# Power_Supply_Section.net
KiCad netlist of a schematic drawn in Altium Designer
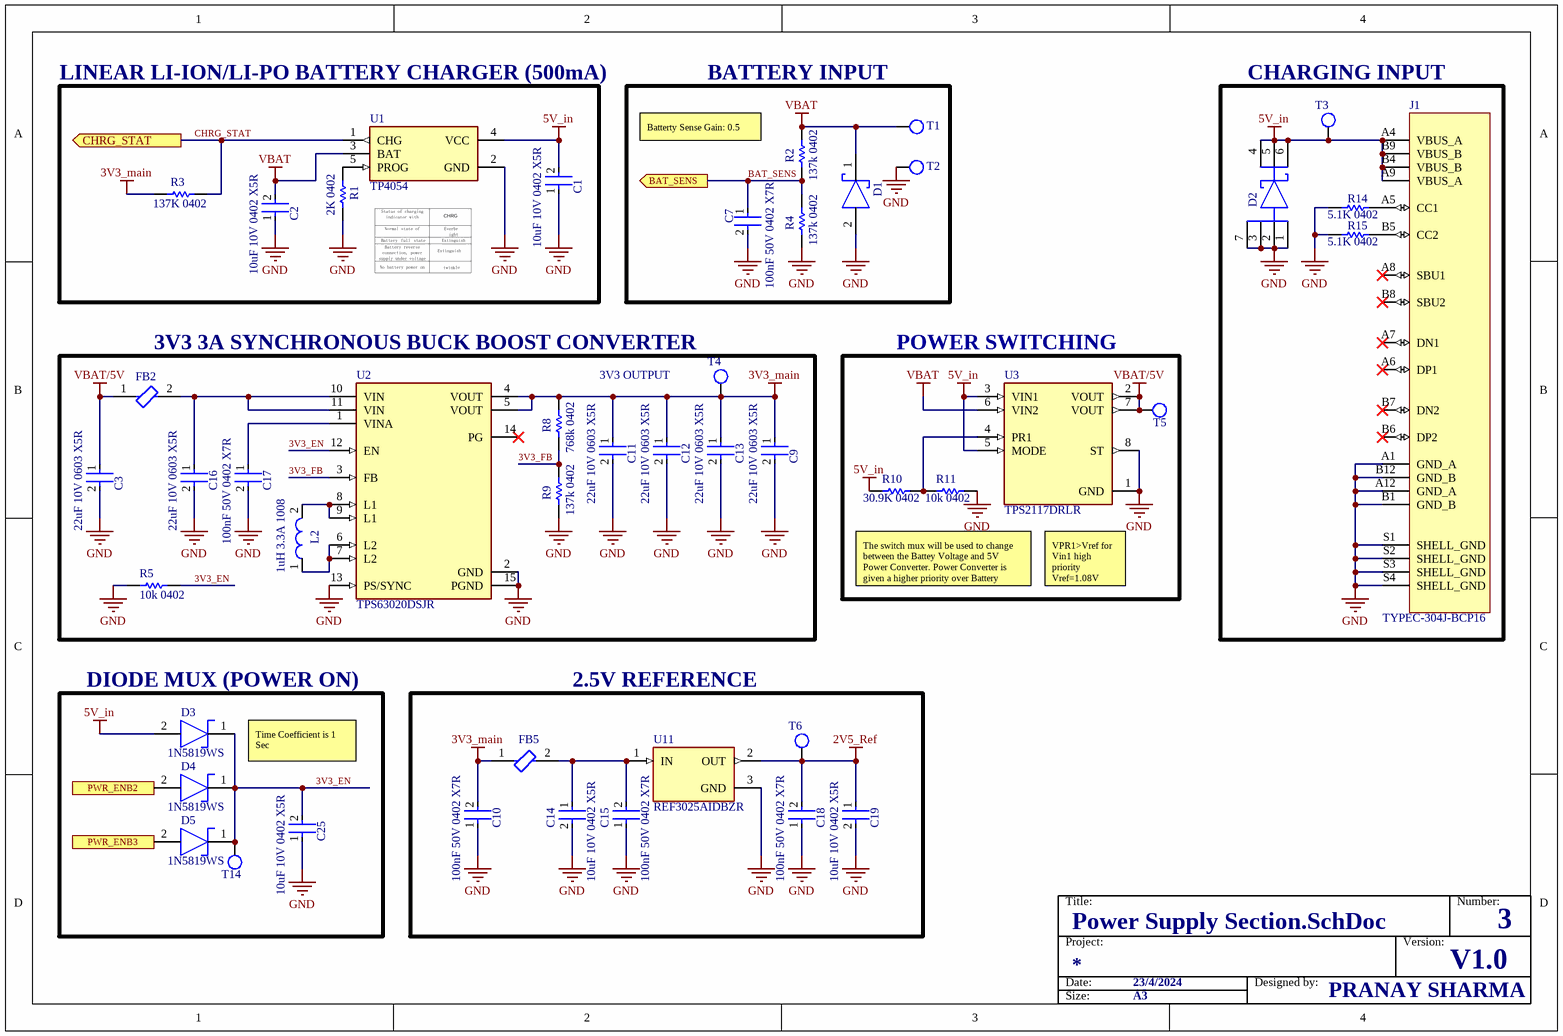
[diagram p0: Power Supply Section.SchDoc]

(export (version "E")
  (design (tool "Eeschema 10.0.6"))
  (components
    (comp (ref "C1")
      (value "10uF 10V 0402 X5R")
      (footprint "Res, Cap, Ind, LED, FB_Lib:0402 IPC CLASS C CAPACITOR")
      (libsource (lib "Capacitor_Lib") (part "10uF 10V 0402 X5R"))
    )
    (comp (ref "C2")
      (value "10uF 10V 0402 X5R")
      (footprint "Res, Cap, Ind, LED, FB_Lib:0402 IPC CLASS C CAPACITOR")
      (libsource (lib "Capacitor_Lib") (part "10uF 10V 0402 X5R"))
    )
    (comp (ref "C3")
      (value "22uF 10V 0603 X5R")
      (footprint "Res, Cap, Ind, LED, FB_Lib:0603 IPC CLASS C CAPACITOR")
      (libsource (lib "Capacitor_Lib") (part "22uF 10V 0603 X5R"))
    )
    (comp (ref "C7")
      (value "100nF 50V 0402 X7R")
      (footprint "Res, Cap, Ind, LED, FB_Lib:0402 IPC CLASS C CAPACITOR")
      (libsource (lib "Capacitor_Lib") (part "100nF 50V 0402 X7R"))
    )
    (comp (ref "C9")
      (value "22uF 10V 0603 X5R")
      (footprint "Res, Cap, Ind, LED, FB_Lib:0603 IPC CLASS C CAPACITOR")
      (libsource (lib "Capacitor_Lib") (part "22uF 10V 0603 X5R"))
    )
    (comp (ref "C10")
      (value "100nF 50V 0402 X7R")
      (footprint "Res, Cap, Ind, LED, FB_Lib:0402 IPC CLASS C CAPACITOR")
      (libsource (lib "Capacitor_Lib") (part "100nF 50V 0402 X7R"))
    )
    (comp (ref "C11")
      (value "22uF 10V 0603 X5R")
      (footprint "Res, Cap, Ind, LED, FB_Lib:0603 IPC CLASS C CAPACITOR")
      (libsource (lib "Capacitor_Lib") (part "22uF 10V 0603 X5R"))
    )
    (comp (ref "C12")
      (value "22uF 10V 0603 X5R")
      (footprint "Res, Cap, Ind, LED, FB_Lib:0603 IPC CLASS C CAPACITOR")
      (libsource (lib "Capacitor_Lib") (part "22uF 10V 0603 X5R"))
    )
    (comp (ref "C13")
      (value "22uF 10V 0603 X5R")
      (footprint "Res, Cap, Ind, LED, FB_Lib:0603 IPC CLASS C CAPACITOR")
      (libsource (lib "Capacitor_Lib") (part "22uF 10V 0603 X5R"))
    )
    (comp (ref "C14")
      (value "10uF 10V 0402 X5R")
      (footprint "Res, Cap, Ind, LED, FB_Lib:0402 IPC CLASS C CAPACITOR")
      (libsource (lib "Capacitor_Lib") (part "10uF 10V 0402 X5R"))
    )
    (comp (ref "C15")
      (value "100nF 50V 0402 X7R")
      (footprint "Res, Cap, Ind, LED, FB_Lib:0402 IPC CLASS C CAPACITOR")
      (libsource (lib "Capacitor_Lib") (part "100nF 50V 0402 X7R"))
    )
    (comp (ref "C16")
      (value "22uF 10V 0603 X5R")
      (footprint "Res, Cap, Ind, LED, FB_Lib:0603 IPC CLASS C CAPACITOR")
      (libsource (lib "Capacitor_Lib") (part "22uF 10V 0603 X5R"))
    )
    (comp (ref "C17")
      (value "100nF 50V 0402 X7R")
      (footprint "Res, Cap, Ind, LED, FB_Lib:0402 IPC CLASS C CAPACITOR")
      (libsource (lib "Capacitor_Lib") (part "100nF 50V 0402 X7R"))
    )
    (comp (ref "C18")
      (value "100nF 50V 0402 X7R")
      (footprint "Res, Cap, Ind, LED, FB_Lib:0402 IPC CLASS C CAPACITOR")
      (libsource (lib "Capacitor_Lib") (part "100nF 50V 0402 X7R"))
    )
    (comp (ref "C19")
      (value "10uF 10V 0402 X5R")
      (footprint "Res, Cap, Ind, LED, FB_Lib:0402 IPC CLASS C CAPACITOR")
      (libsource (lib "Capacitor_Lib") (part "10uF 10V 0402 X5R"))
    )
    (comp (ref "C25")
      (value "10uF 10V 0402 X5R")
      (footprint "Res, Cap, Ind, LED, FB_Lib:0402 IPC CLASS C CAPACITOR")
      (libsource (lib "Capacitor_Lib") (part "10uF 10V 0402 X5R"))
    )
    (comp (ref "D1")
      (value "SP3031-01ETG")
      (footprint "Res, Cap, Ind, LED, FB_Lib:SOD882 IPC-C")
      (libsource (lib "Diodes_Lib") (part "SP3031-01ETG"))
    )
    (comp (ref "D2")
      (value "TVS0500DRVR")
      (footprint "Res, Cap, Ind, LED, FB_Lib:DRV0006A IPC-C")
      (libsource (lib "Diodes_Lib") (part "TVS0500DRVR"))
    )
    (comp (ref "D3")
      (value "1N5819WS")
      (footprint "Res, Cap, Ind, LED, FB_Lib:SOD-323 IPC-C")
      (libsource (lib "Diodes_Lib") (part "1N5819WS"))
    )
    (comp (ref "D4")
      (value "1N5819WS")
      (footprint "Res, Cap, Ind, LED, FB_Lib:SOD-323 IPC-C")
      (libsource (lib "Diodes_Lib") (part "1N5819WS"))
    )
    (comp (ref "D5")
      (value "1N5819WS")
      (footprint "Res, Cap, Ind, LED, FB_Lib:SOD-323 IPC-C")
      (libsource (lib "Diodes_Lib") (part "1N5819WS"))
    )
    (comp (ref "FB2")
      (value "BLM21SP111SN1D")
      (footprint "Res, Cap, Ind, LED, FB_Lib:0603 IPC CLASS C FERRITE BEAD")
      (libsource (lib "Ferrite_Bead_Lib") (part "BLM21SP111SN1D"))
    )
    (comp (ref "FB5")
      (value "BLM15AX102SN1D")
      (footprint "Res, Cap, Ind, LED, FB_Lib:0402 IPC CLASS C FERRITE BEAD")
      (libsource (lib "Ferrite_Bead_Lib") (part "BLM15AX102SN1D"))
    )
    (comp (ref "J1")
      (value "TYPEC-304J-BCP16")
      (footprint "VALCON_CSP-USC16-TR")
      (libsource (lib "V1.0") (part "USB Type C"))
    )
    (comp (ref "L2")
      (value "1uH 3.3A 1008")
      (footprint "Res, Cap, Ind, LED, FB_Lib:1008 Inductor IPC-C")
      (libsource (lib "Inductor_Lib") (part "DFE252012F-1R0M=P2"))
    )
    (comp (ref "R1")
      (value "2K 0402")
      (footprint "Res, Cap, Ind, LED, FB_Lib:0402 IPC CLASS C RESISTOR")
      (libsource (lib "Resistor_Lib") (part "2K 1% 0402"))
    )
    (comp (ref "R2")
      (value "137k 0402")
      (footprint "Res, Cap, Ind, LED, FB_Lib:0402 IPC CLASS C RESISTOR")
      (libsource (lib "Resistor_Lib") (part "10k 1% 0402"))
    )
    (comp (ref "R3")
      (value "137K 0402")
      (footprint "Res, Cap, Ind, LED, FB_Lib:0402 IPC CLASS C RESISTOR")
      (libsource (lib "Resistor_Lib") (part "137K 1% 0402"))
    )
    (comp (ref "R4")
      (value "137k 0402")
      (footprint "Res, Cap, Ind, LED, FB_Lib:0402 IPC CLASS C RESISTOR")
      (libsource (lib "Resistor_Lib") (part "10k 1% 0402"))
    )
    (comp (ref "R5")
      (value "10k 0402")
      (footprint "Res, Cap, Ind, LED, FB_Lib:0402 IPC CLASS C RESISTOR")
      (libsource (lib "Resistor_Lib") (part "10k 1% 0402"))
    )
    (comp (ref "R8")
      (value "768k 0402")
      (footprint "Res, Cap, Ind, LED, FB_Lib:0402 IPC CLASS C RESISTOR")
      (libsource (lib "Resistor_Lib") (part "10k 1% 0402"))
    )
    (comp (ref "R9")
      (value "137k 0402")
      (footprint "Res, Cap, Ind, LED, FB_Lib:0402 IPC CLASS C RESISTOR")
      (libsource (lib "Resistor_Lib") (part "10k 1% 0402"))
    )
    (comp (ref "R10")
      (value "30.9K 0402")
      (footprint "Res, Cap, Ind, LED, FB_Lib:0402 IPC CLASS C RESISTOR")
      (libsource (lib "Resistor_Lib") (part "30.9K 1%  0402"))
    )
    (comp (ref "R11")
      (value "10k 0402")
      (footprint "Res, Cap, Ind, LED, FB_Lib:0402 IPC CLASS C RESISTOR")
      (libsource (lib "Resistor_Lib") (part "10k 1% 0402"))
    )
    (comp (ref "R14")
      (value "5.1K 0402")
      (footprint "Res, Cap, Ind, LED, FB_Lib:0402 IPC CLASS C RESISTOR")
      (libsource (lib "Resistor_Lib") (part "5.1K 1% 0402"))
    )
    (comp (ref "R15")
      (value "5.1K 0402")
      (footprint "Res, Cap, Ind, LED, FB_Lib:0402 IPC CLASS C RESISTOR")
      (libsource (lib "Resistor_Lib") (part "5.1K 1% 0402"))
    )
    (comp (ref "T1")
      (value "Test Point TH")
      (footprint "Miscellaneous_Lib:Test Point TH")
      (libsource (lib "Miscellaneous_Lib") (part "Test Point TH"))
    )
    (comp (ref "T2")
      (value "Test Point TH")
      (footprint "Miscellaneous_Lib:Test Point TH")
      (libsource (lib "Miscellaneous_Lib") (part "Test Point TH"))
    )
    (comp (ref "T3")
      (value "TP")
      (footprint "Miscellaneous_Lib:Testpoint1")
      (libsource (lib "Miscellaneous_Lib") (part "Testpoint1"))
    )
    (comp (ref "T4")
      (value "TP")
      (footprint "Miscellaneous_Lib:Testpoint1")
      (libsource (lib "Miscellaneous_Lib") (part "Testpoint1"))
    )
    (comp (ref "T5")
      (value "TP")
      (footprint "Miscellaneous_Lib:Testpoint1")
      (libsource (lib "Miscellaneous_Lib") (part "Testpoint1"))
    )
    (comp (ref "T6")
      (value "TP")
      (footprint "Miscellaneous_Lib:Testpoint1")
      (libsource (lib "Miscellaneous_Lib") (part "Testpoint1"))
    )
    (comp (ref "T14")
      (value "TP")
      (footprint "Miscellaneous_Lib:Testpoint1")
      (libsource (lib "Miscellaneous_Lib") (part "Testpoint1"))
    )
    (comp (ref "U1")
      (value "TP4054")
      (footprint "Integrated_Circuits_Lib:DBV0005A IPC-C")
      (libsource (lib "Integrated_Circuits_Lib") (part "TP4054"))
    )
    (comp (ref "U2")
      (value "TPS63020DSJR")
      (footprint "FP-DSJ0014A-MFG")
      (libsource (lib "Altium Content Vault") (part "ca84f4b88d1e031d86a58c77b9c066d"))
    )
    (comp (ref "U3")
      (value "TPS2117DRLR")
      (footprint "Integrated_Circuits_Lib:DRL0008A IPC-C")
      (libsource (lib "Integrated_Circuits_Lib") (part "TPS2117DRLR"))
    )
    (comp (ref "U11")
      (value "REF3025AIDBZR")
      (footprint "Integrated_Circuits_Lib:SOT23-IPC_C")
      (libsource (lib "Integrated_Circuits_Lib") (part "REF3025AIDBZR"))
    )
  )
  (nets
    (net (code "1") (name "/3V3_EN") (class "Default")
      (node (ref "C25") (pin "2") (pinfunction "2_2") (pintype "passive"))
      (node (ref "D3") (pin "1") (pinfunction "C_1") (pintype "passive"))
      (node (ref "D4") (pin "1") (pinfunction "C_1") (pintype "passive"))
      (node (ref "D5") (pin "1") (pinfunction "C_1") (pintype "passive"))
      (node (ref "R5") (pin "1") (pinfunction "1_1") (pintype "passive"))
      (node (ref "T14") (pin "0") (pinfunction "0_0") (pintype "passive"))
      (node (ref "U2") (pin "12") (pinfunction "EN_12") (pintype "input"))
    )
    (net (code "2") (name "/3V3_FB") (class "Default")
      (node (ref "R8") (pin "2") (pinfunction "2_2") (pintype "passive"))
      (node (ref "R9") (pin "2") (pinfunction "2_2") (pintype "passive"))
      (node (ref "U2") (pin "3") (pinfunction "FB_3") (pintype "input"))
    )
    (net (code "3") (name "/BAT_SENS") (class "Default")
      (node (ref "C7") (pin "1") (pinfunction "1_1") (pintype "passive"))
      (node (ref "R2") (pin "1") (pinfunction "1_1") (pintype "passive"))
      (node (ref "R4") (pin "2") (pinfunction "2_2") (pintype "passive"))
    )
    (net (code "4") (name "/CHRG_STAT") (class "Default")
      (node (ref "R3") (pin "2") (pinfunction "2_2") (pintype "passive"))
      (node (ref "U1") (pin "1") (pinfunction "CHG_1") (pintype "output"))
    )
    (net (code "5") (name "/PWR_ENB2") (class "Default")
      (node (ref "D4") (pin "2") (pinfunction "A_2") (pintype "passive"))
    )
    (net (code "6") (name "/PWR_ENB3") (class "Default")
      (node (ref "D5") (pin "2") (pinfunction "A_2") (pintype "passive"))
    )
    (net (code "7") (name "2V5_Ref") (class "Default")
      (node (ref "C18") (pin "2") (pinfunction "2_2") (pintype "passive"))
      (node (ref "C19") (pin "1") (pinfunction "1_1") (pintype "passive"))
      (node (ref "T6") (pin "0") (pinfunction "0_0") (pintype "passive"))
      (node (ref "U11") (pin "2") (pinfunction "OUT_2") (pintype "output"))
    )
    (net (code "8") (name "3V3_main") (class "Default")
      (node (ref "C10") (pin "2") (pinfunction "2_2") (pintype "passive"))
      (node (ref "C11") (pin "1") (pinfunction "1_1") (pintype "passive"))
      (node (ref "C12") (pin "1") (pinfunction "1_1") (pintype "passive"))
      (node (ref "C13") (pin "1") (pinfunction "1_1") (pintype "passive"))
      (node (ref "C9") (pin "1") (pinfunction "1_1") (pintype "passive"))
      (node (ref "FB5") (pin "1") (pinfunction "1_1") (pintype "passive"))
      (node (ref "R3") (pin "1") (pinfunction "1_1") (pintype "passive"))
      (node (ref "R8") (pin "1") (pinfunction "1_1") (pintype "passive"))
      (node (ref "T4") (pin "0") (pinfunction "0_0") (pintype "passive"))
      (node (ref "U2") (pin "4") (pinfunction "VOUT_4") (pintype "power_in"))
      (node (ref "U2") (pin "5") (pinfunction "VOUT_5") (pintype "power_in"))
    )
    (net (code "9") (name "5V_in") (class "Default")
      (node (ref "C1") (pin "2") (pinfunction "2_2") (pintype "passive"))
      (node (ref "D2") (pin "4") (pinfunction "4_4") (pintype "passive"))
      (node (ref "D2") (pin "5") (pinfunction "5_5") (pintype "passive"))
      (node (ref "D2") (pin "6") (pinfunction "6_6") (pintype "passive"))
      (node (ref "D3") (pin "2") (pinfunction "A_2") (pintype "passive"))
      (node (ref "J1") (pin "A4") (pinfunction "VBUS_A_A4") (pintype "power_in"))
      (node (ref "J1") (pin "A9") (pinfunction "VBUS_A_A9") (pintype "power_in"))
      (node (ref "J1") (pin "B4") (pinfunction "VBUS_B_B4") (pintype "power_in"))
      (node (ref "J1") (pin "B9") (pinfunction "VBUS_B_B9") (pintype "power_in"))
      (node (ref "R10") (pin "2") (pinfunction "2_2") (pintype "passive"))
      (node (ref "T3") (pin "0") (pinfunction "0_0") (pintype "passive"))
      (node (ref "U1") (pin "4") (pinfunction "VCC_4") (pintype "power_in"))
      (node (ref "U3") (pin "3") (pinfunction "VIN1_3") (pintype "input"))
      (node (ref "U3") (pin "5") (pinfunction "MODE_5") (pintype "input"))
    )
    (net (code "10") (name "GND") (class "Default")
      (node (ref "C1") (pin "1") (pinfunction "1_1") (pintype "passive"))
      (node (ref "C10") (pin "1") (pinfunction "1_1") (pintype "passive"))
      (node (ref "C11") (pin "2") (pinfunction "2_2") (pintype "passive"))
      (node (ref "C12") (pin "2") (pinfunction "2_2") (pintype "passive"))
      (node (ref "C13") (pin "2") (pinfunction "2_2") (pintype "passive"))
      (node (ref "C14") (pin "2") (pinfunction "2_2") (pintype "passive"))
      (node (ref "C15") (pin "1") (pinfunction "1_1") (pintype "passive"))
      (node (ref "C16") (pin "2") (pinfunction "2_2") (pintype "passive"))
      (node (ref "C17") (pin "2") (pinfunction "2_2") (pintype "passive"))
      (node (ref "C18") (pin "1") (pinfunction "1_1") (pintype "passive"))
      (node (ref "C19") (pin "2") (pinfunction "2_2") (pintype "passive"))
      (node (ref "C2") (pin "1") (pinfunction "1_1") (pintype "passive"))
      (node (ref "C25") (pin "1") (pinfunction "1_1") (pintype "passive"))
      (node (ref "C3") (pin "2") (pinfunction "2_2") (pintype "passive"))
      (node (ref "C7") (pin "2") (pinfunction "2_2") (pintype "passive"))
      (node (ref "C9") (pin "2") (pinfunction "2_2") (pintype "passive"))
      (node (ref "D1") (pin "2") (pinfunction "A_2") (pintype "passive"))
      (node (ref "D2") (pin "1") (pinfunction "C_1") (pintype "passive"))
      (node (ref "D2") (pin "2") (pinfunction "A_2") (pintype "passive"))
      (node (ref "D2") (pin "3") (pinfunction "3_3") (pintype "passive"))
      (node (ref "D2") (pin "7") (pinfunction "7_7") (pintype "passive"))
      (node (ref "J1") (pin "A1") (pinfunction "GND_A_A1") (pintype "power_in"))
      (node (ref "J1") (pin "A12") (pinfunction "GND_A_A12") (pintype "power_in"))
      (node (ref "J1") (pin "B1") (pinfunction "GND_B_B1") (pintype "power_in"))
      (node (ref "J1") (pin "B12") (pinfunction "GND_B_B12") (pintype "power_in"))
      (node (ref "J1") (pin "S1") (pinfunction "SHELL_GND_S1") (pintype "power_in"))
      (node (ref "J1") (pin "S2") (pinfunction "SHELL_GND_S2") (pintype "power_in"))
      (node (ref "J1") (pin "S3") (pinfunction "SHELL_GND_S3") (pintype "power_in"))
      (node (ref "J1") (pin "S4") (pinfunction "SHELL_GND_S4") (pintype "power_in"))
      (node (ref "R1") (pin "2") (pinfunction "2_2") (pintype "passive"))
      (node (ref "R11") (pin "1") (pinfunction "1_1") (pintype "passive"))
      (node (ref "R14") (pin "1") (pinfunction "1_1") (pintype "passive"))
      (node (ref "R15") (pin "1") (pinfunction "1_1") (pintype "passive"))
      (node (ref "R4") (pin "1") (pinfunction "1_1") (pintype "passive"))
      (node (ref "R5") (pin "2") (pinfunction "2_2") (pintype "passive"))
      (node (ref "R9") (pin "1") (pinfunction "1_1") (pintype "passive"))
      (node (ref "T2") (pin "0") (pinfunction "0_0") (pintype "passive"))
      (node (ref "U1") (pin "2") (pinfunction "GND_2") (pintype "power_in"))
      (node (ref "U11") (pin "3") (pinfunction "GND_3") (pintype "power_in"))
      (node (ref "U2") (pin "13") (pinfunction "PS/SYNC_13") (pintype "input"))
      (node (ref "U2") (pin "15") (pinfunction "PGND_15") (pintype "power_in"))
      (node (ref "U2") (pin "2") (pinfunction "GND_2") (pintype "power_in"))
      (node (ref "U3") (pin "1") (pinfunction "GND_1") (pintype "power_in"))
      (node (ref "U3") (pin "8") (pinfunction "ST_8") (pintype "output"))
    )
    (net (code "11") (name "Net-(C16-Pad1)") (class "Default")
      (node (ref "C16") (pin "1") (pinfunction "1_1") (pintype "passive"))
      (node (ref "FB2") (pin "2") (pinfunction "2_2") (pintype "passive"))
      (node (ref "U2") (pin "10") (pinfunction "VIN_10") (pintype "power_in"))
      (node (ref "U2") (pin "11") (pinfunction "VIN_11") (pintype "power_in"))
    )
    (net (code "12") (name "Net-(J1-CC1)") (class "Default")
      (node (ref "J1") (pin "A5") (pinfunction "CC1_A5") (pintype "bidirectional"))
      (node (ref "R14") (pin "2") (pinfunction "2_2") (pintype "passive"))
    )
    (net (code "13") (name "Net-(J1-CC2)") (class "Default")
      (node (ref "J1") (pin "B5") (pinfunction "CC2_B5") (pintype "bidirectional"))
      (node (ref "R15") (pin "2") (pinfunction "2_2") (pintype "passive"))
    )
    (net (code "14") (name "Net-(L2-Pad1)") (class "Default")
      (node (ref "L2") (pin "1") (pinfunction "1_1") (pintype "passive"))
      (node (ref "U2") (pin "6") (pinfunction "L2_6") (pintype "input"))
      (node (ref "U2") (pin "7") (pinfunction "L2_7") (pintype "input"))
    )
    (net (code "15") (name "Net-(L2-Pad2)") (class "Default")
      (node (ref "L2") (pin "2") (pinfunction "2_2") (pintype "passive"))
      (node (ref "U2") (pin "8") (pinfunction "L1_8") (pintype "input"))
      (node (ref "U2") (pin "9") (pinfunction "L1_9") (pintype "input"))
    )
    (net (code "16") (name "Net-(U1-PROG)") (class "Default")
      (node (ref "R1") (pin "1") (pinfunction "1_1") (pintype "passive"))
      (node (ref "U1") (pin "5") (pinfunction "PROG_5") (pintype "input"))
    )
    (net (code "17") (name "Net-(U2-VINA)") (class "Default")
      (node (ref "C17") (pin "1") (pinfunction "1_1") (pintype "passive"))
      (node (ref "U2") (pin "1") (pinfunction "VINA_1") (pintype "power_in"))
    )
    (net (code "18") (name "Net-(U3-PR1)") (class "Default")
      (node (ref "R10") (pin "1") (pinfunction "1_1") (pintype "passive"))
      (node (ref "R11") (pin "2") (pinfunction "2_2") (pintype "passive"))
      (node (ref "U3") (pin "4") (pinfunction "PR1_4") (pintype "input"))
    )
    (net (code "19") (name "Net-(U11-IN)") (class "Default")
      (node (ref "C14") (pin "1") (pinfunction "1_1") (pintype "passive"))
      (node (ref "C15") (pin "2") (pinfunction "2_2") (pintype "passive"))
      (node (ref "FB5") (pin "2") (pinfunction "2_2") (pintype "passive"))
      (node (ref "U11") (pin "1") (pinfunction "IN_1") (pintype "input"))
    )
    (net (code "20") (name "VBAT") (class "Default")
      (node (ref "C2") (pin "2") (pinfunction "2_2") (pintype "passive"))
      (node (ref "D1") (pin "1") (pinfunction "C_1") (pintype "passive"))
      (node (ref "R2") (pin "2") (pinfunction "2_2") (pintype "passive"))
      (node (ref "T1") (pin "0") (pinfunction "0_0") (pintype "passive"))
      (node (ref "U1") (pin "3") (pinfunction "BAT_3") (pintype "power_in"))
      (node (ref "U3") (pin "6") (pinfunction "VIN2_6") (pintype "input"))
    )
    (net (code "21") (name "VBAT{slash}5V") (class "Default")
      (node (ref "C3") (pin "1") (pinfunction "1_1") (pintype "passive"))
      (node (ref "FB2") (pin "1") (pinfunction "1_1") (pintype "passive"))
      (node (ref "T5") (pin "0") (pinfunction "0_0") (pintype "passive"))
      (node (ref "U3") (pin "2") (pinfunction "VOUT_2") (pintype "output"))
      (node (ref "U3") (pin "7") (pinfunction "VOUT_7") (pintype "output"))
    )
    (net (code "22") (name "unconnected-(J1-DN1-PadA7)") (class "Default")
      (node (ref "J1") (pin "A7") (pinfunction "DN1_A7") (pintype "bidirectional+no_connect"))
    )
    (net (code "23") (name "unconnected-(J1-DN2-PadB7)") (class "Default")
      (node (ref "J1") (pin "B7") (pinfunction "DN2_B7") (pintype "bidirectional+no_connect"))
    )
    (net (code "24") (name "unconnected-(J1-DP1-PadA6)") (class "Default")
      (node (ref "J1") (pin "A6") (pinfunction "DP1_A6") (pintype "bidirectional+no_connect"))
    )
    (net (code "25") (name "unconnected-(J1-DP2-PadB6)") (class "Default")
      (node (ref "J1") (pin "B6") (pinfunction "DP2_B6") (pintype "bidirectional+no_connect"))
    )
    (net (code "26") (name "unconnected-(J1-SBU1-PadA8)") (class "Default")
      (node (ref "J1") (pin "A8") (pinfunction "SBU1_A8") (pintype "bidirectional+no_connect"))
    )
    (net (code "27") (name "unconnected-(J1-SBU2-PadB8)") (class "Default")
      (node (ref "J1") (pin "B8") (pinfunction "SBU2_B8") (pintype "bidirectional+no_connect"))
    )
    (net (code "28") (name "unconnected-(U2-PG-Pad14)") (class "Default")
      (node (ref "U2") (pin "14") (pinfunction "PG_14") (pintype "open_collector+no_connect"))
    )
  )
)
